# Intan_32.net
KiCad netlist of a schematic drawn in EAGLE
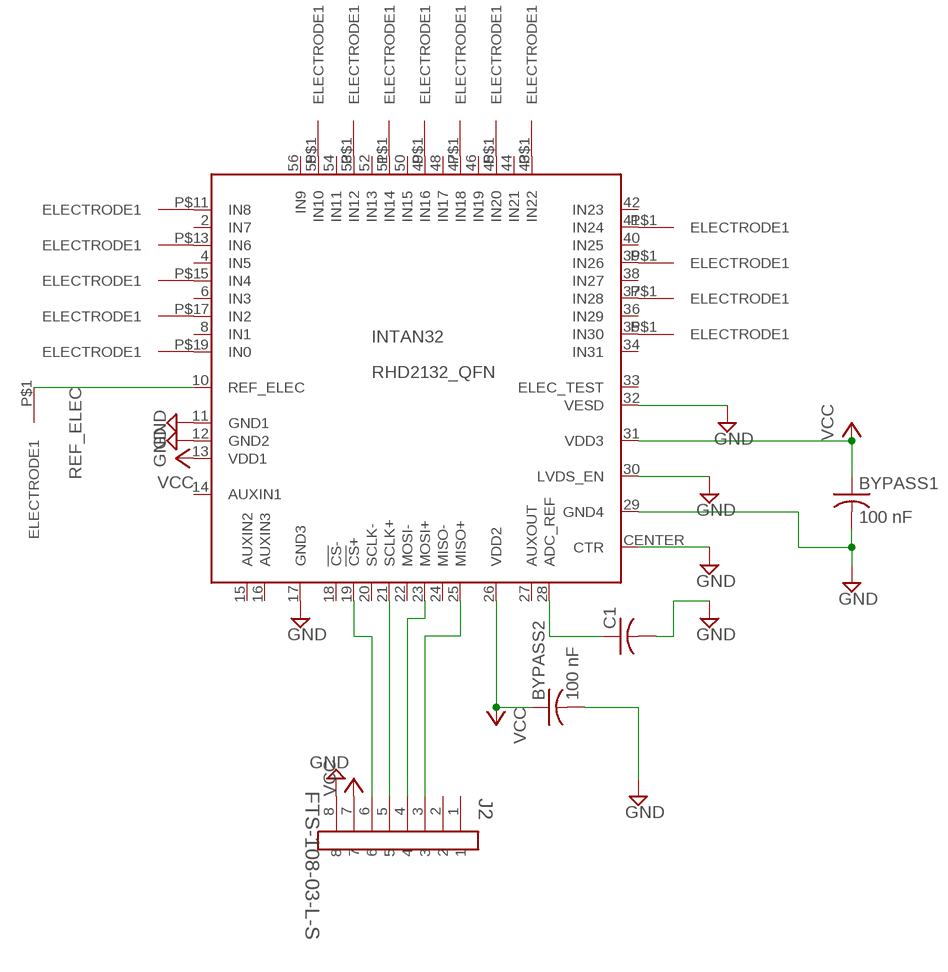
[diagram p0: schematic, sheet 1]

(export (version "E")
  (design (tool "Eeschema 10.0.6"))
  (components
    (comp (ref "BYPASS1")
      (value "100 nF")
      (footprint "eagle-import:C0402")
      (libsource (lib "eagle-import") (part "C-USC0402"))
    )
    (comp (ref "BYPASS2")
      (value "100 nF")
      (footprint "eagle-import:C0402")
      (libsource (lib "eagle-import") (part "C-USC0402"))
    )
    (comp (ref "C1")
      (value "C-USC0402")
      (footprint "eagle-import:C0402")
      (libsource (lib "eagle-import") (part "C-USC0402"))
    )
    (comp (ref "INTAN32")
      (value "RHD2132_QFN")
      (footprint "eagle-import:QFN56_8_X_8_LARGE")
      (libsource (lib "eagle-import") (part "RHD2132_QFN"))
    )
    (comp (ref "J2")
      (value "FTS-108-03-L-S")
      (footprint "eagle-import:SAMTEC_FTS-108-03-S")
      (fields (field (name "MPN") "FTS-108-03-L-D"))
      (libsource (lib "eagle-import") (part "FTS-108-03-L-S"))
    )
    (comp (ref "REF_ELEC")
      (value "INTAN_ELECTRODE_HOLE_2323MIL")
      (footprint "eagle-import:INTAN_ELECTRODE_HOLE_23")
      (libsource (lib "eagle-import") (part "INTAN_ELECTRODE_HOLE_2323MIL"))
    )
    (comp (ref "U$1")
      (value "INTAN_ELECTRODE_HOLE_2323MIL")
      (footprint "eagle-import:INTAN_ELECTRODE_HOLE_23")
      (libsource (lib "eagle-import") (part "INTAN_ELECTRODE_HOLE_2323MIL"))
    )
    (comp (ref "U$2")
      (value "INTAN_ELECTRODE_HOLE_2323MIL")
      (footprint "eagle-import:INTAN_ELECTRODE_HOLE_23")
      (libsource (lib "eagle-import") (part "INTAN_ELECTRODE_HOLE_2323MIL"))
    )
    (comp (ref "U$3")
      (value "INTAN_ELECTRODE_HOLE_2323MIL")
      (footprint "eagle-import:INTAN_ELECTRODE_HOLE_23")
      (libsource (lib "eagle-import") (part "INTAN_ELECTRODE_HOLE_2323MIL"))
    )
    (comp (ref "U$4")
      (value "INTAN_ELECTRODE_HOLE_2323MIL")
      (footprint "eagle-import:INTAN_ELECTRODE_HOLE_23")
      (libsource (lib "eagle-import") (part "INTAN_ELECTRODE_HOLE_2323MIL"))
    )
    (comp (ref "U$5")
      (value "INTAN_ELECTRODE_HOLE_2323MIL")
      (footprint "eagle-import:INTAN_ELECTRODE_HOLE_23")
      (libsource (lib "eagle-import") (part "INTAN_ELECTRODE_HOLE_2323MIL"))
    )
    (comp (ref "U$6")
      (value "INTAN_ELECTRODE_HOLE_2323MIL")
      (footprint "eagle-import:INTAN_ELECTRODE_HOLE_23")
      (libsource (lib "eagle-import") (part "INTAN_ELECTRODE_HOLE_2323MIL"))
    )
    (comp (ref "U$7")
      (value "INTAN_ELECTRODE_HOLE_2323MIL")
      (footprint "eagle-import:INTAN_ELECTRODE_HOLE_23")
      (libsource (lib "eagle-import") (part "INTAN_ELECTRODE_HOLE_2323MIL"))
    )
    (comp (ref "U$8")
      (value "INTAN_ELECTRODE_HOLE_2323MIL")
      (footprint "eagle-import:INTAN_ELECTRODE_HOLE_23")
      (libsource (lib "eagle-import") (part "INTAN_ELECTRODE_HOLE_2323MIL"))
    )
    (comp (ref "U$9")
      (value "INTAN_ELECTRODE_HOLE_2323MIL")
      (footprint "eagle-import:INTAN_ELECTRODE_HOLE_23")
      (libsource (lib "eagle-import") (part "INTAN_ELECTRODE_HOLE_2323MIL"))
    )
    (comp (ref "U$10")
      (value "INTAN_ELECTRODE_HOLE_2323MIL")
      (footprint "eagle-import:INTAN_ELECTRODE_HOLE_23")
      (libsource (lib "eagle-import") (part "INTAN_ELECTRODE_HOLE_2323MIL"))
    )
    (comp (ref "U$11")
      (value "INTAN_ELECTRODE_HOLE_2323MIL")
      (footprint "eagle-import:INTAN_ELECTRODE_HOLE_23")
      (libsource (lib "eagle-import") (part "INTAN_ELECTRODE_HOLE_2323MIL"))
    )
    (comp (ref "U$12")
      (value "INTAN_ELECTRODE_HOLE_2323MIL")
      (footprint "eagle-import:INTAN_ELECTRODE_HOLE_23")
      (libsource (lib "eagle-import") (part "INTAN_ELECTRODE_HOLE_2323MIL"))
    )
    (comp (ref "U$13")
      (value "INTAN_ELECTRODE_HOLE_2323MIL")
      (footprint "eagle-import:INTAN_ELECTRODE_HOLE_23")
      (libsource (lib "eagle-import") (part "INTAN_ELECTRODE_HOLE_2323MIL"))
    )
    (comp (ref "U$14")
      (value "INTAN_ELECTRODE_HOLE_2323MIL")
      (footprint "eagle-import:INTAN_ELECTRODE_HOLE_23")
      (libsource (lib "eagle-import") (part "INTAN_ELECTRODE_HOLE_2323MIL"))
    )
    (comp (ref "U$15")
      (value "INTAN_ELECTRODE_HOLE_2323MIL")
      (footprint "eagle-import:INTAN_ELECTRODE_HOLE_23")
      (libsource (lib "eagle-import") (part "INTAN_ELECTRODE_HOLE_2323MIL"))
    )
    (comp (ref "U$16")
      (value "INTAN_ELECTRODE_HOLE_2323MIL")
      (footprint "eagle-import:INTAN_ELECTRODE_HOLE_23")
      (libsource (lib "eagle-import") (part "INTAN_ELECTRODE_HOLE_2323MIL"))
    )
  )
  (nets
    (net (code "1") (name "/REF_ELEC") (class "Default")
      (node (ref "INTAN32") (pin "10") (pinfunction "REF_ELEC_10") (pintype "input"))
      (node (ref "REF_ELEC") (pin "P$1") (pinfunction "ELECTRODE1_P$1") (pintype "bidirectional"))
    )
    (net (code "2") (name "GND") (class "Default")
      (node (ref "BYPASS1") (pin "2") (pinfunction "2_2") (pintype "passive"))
      (node (ref "BYPASS2") (pin "2") (pinfunction "2_2") (pintype "passive"))
      (node (ref "C1") (pin "2") (pinfunction "2_2") (pintype "passive"))
      (node (ref "INTAN32") (pin "11") (pinfunction "GND1_11") (pintype "power_in"))
      (node (ref "INTAN32") (pin "12") (pinfunction "GND2_12") (pintype "power_in"))
      (node (ref "INTAN32") (pin "17") (pinfunction "GND3_17") (pintype "power_in"))
      (node (ref "INTAN32") (pin "29") (pinfunction "GND4_29") (pintype "power_in"))
      (node (ref "INTAN32") (pin "30") (pinfunction "LVDS_EN_30") (pintype "input"))
      (node (ref "INTAN32") (pin "32") (pinfunction "VESD_32") (pintype "power_in"))
      (node (ref "INTAN32") (pin "CENTER") (pinfunction "CTR_CENTER") (pintype "power_in"))
      (node (ref "J2") (pin "8") (pinfunction "8_8") (pintype "passive"))
    )
    (net (code "3") (name "Net-(INTAN32-ADC_REF)") (class "Default")
      (node (ref "C1") (pin "1") (pinfunction "1_1") (pintype "passive"))
      (node (ref "INTAN32") (pin "28") (pinfunction "ADC_REF_28") (pintype "passive"))
    )
    (net (code "4") (name "Net-(INTAN32-IN0)") (class "Default")
      (node (ref "INTAN32") (pin "9") (pinfunction "IN0_9") (pintype "input"))
      (node (ref "U$1") (pin "P$1") (pinfunction "ELECTRODE1_P$1") (pintype "bidirectional"))
    )
    (net (code "5") (name "Net-(INTAN32-IN2)") (class "Default")
      (node (ref "INTAN32") (pin "7") (pinfunction "IN2_7") (pintype "input"))
      (node (ref "U$2") (pin "P$1") (pinfunction "ELECTRODE1_P$1") (pintype "bidirectional"))
    )
    (net (code "6") (name "Net-(INTAN32-IN4)") (class "Default")
      (node (ref "INTAN32") (pin "5") (pinfunction "IN4_5") (pintype "input"))
      (node (ref "U$3") (pin "P$1") (pinfunction "ELECTRODE1_P$1") (pintype "bidirectional"))
    )
    (net (code "7") (name "Net-(INTAN32-IN6)") (class "Default")
      (node (ref "INTAN32") (pin "3") (pinfunction "IN6_3") (pintype "input"))
      (node (ref "U$4") (pin "P$1") (pinfunction "ELECTRODE1_P$1") (pintype "bidirectional"))
    )
    (net (code "8") (name "Net-(INTAN32-IN8)") (class "Default")
      (node (ref "INTAN32") (pin "1") (pinfunction "IN8_1") (pintype "input"))
      (node (ref "U$5") (pin "P$1") (pinfunction "ELECTRODE1_P$1") (pintype "bidirectional"))
    )
    (net (code "9") (name "Net-(INTAN32-IN10)") (class "Default")
      (node (ref "INTAN32") (pin "55") (pinfunction "IN10_55") (pintype "input"))
      (node (ref "U$6") (pin "P$1") (pinfunction "ELECTRODE1_P$1") (pintype "bidirectional"))
    )
    (net (code "10") (name "Net-(INTAN32-IN12)") (class "Default")
      (node (ref "INTAN32") (pin "53") (pinfunction "IN12_53") (pintype "input"))
      (node (ref "U$7") (pin "P$1") (pinfunction "ELECTRODE1_P$1") (pintype "bidirectional"))
    )
    (net (code "11") (name "Net-(INTAN32-IN14)") (class "Default")
      (node (ref "INTAN32") (pin "51") (pinfunction "IN14_51") (pintype "input"))
      (node (ref "U$8") (pin "P$1") (pinfunction "ELECTRODE1_P$1") (pintype "bidirectional"))
    )
    (net (code "12") (name "Net-(INTAN32-IN16)") (class "Default")
      (node (ref "INTAN32") (pin "49") (pinfunction "IN16_49") (pintype "input"))
      (node (ref "U$9") (pin "P$1") (pinfunction "ELECTRODE1_P$1") (pintype "bidirectional"))
    )
    (net (code "13") (name "Net-(INTAN32-IN18)") (class "Default")
      (node (ref "INTAN32") (pin "47") (pinfunction "IN18_47") (pintype "input"))
      (node (ref "U$10") (pin "P$1") (pinfunction "ELECTRODE1_P$1") (pintype "bidirectional"))
    )
    (net (code "14") (name "Net-(INTAN32-IN20)") (class "Default")
      (node (ref "INTAN32") (pin "45") (pinfunction "IN20_45") (pintype "input"))
      (node (ref "U$11") (pin "P$1") (pinfunction "ELECTRODE1_P$1") (pintype "bidirectional"))
    )
    (net (code "15") (name "Net-(INTAN32-IN22)") (class "Default")
      (node (ref "INTAN32") (pin "43") (pinfunction "IN22_43") (pintype "input"))
      (node (ref "U$12") (pin "P$1") (pinfunction "ELECTRODE1_P$1") (pintype "bidirectional"))
    )
    (net (code "16") (name "Net-(INTAN32-IN24)") (class "Default")
      (node (ref "INTAN32") (pin "41") (pinfunction "IN24_41") (pintype "input"))
      (node (ref "U$13") (pin "P$1") (pinfunction "ELECTRODE1_P$1") (pintype "bidirectional"))
    )
    (net (code "17") (name "Net-(INTAN32-IN26)") (class "Default")
      (node (ref "INTAN32") (pin "39") (pinfunction "IN26_39") (pintype "input"))
      (node (ref "U$14") (pin "P$1") (pinfunction "ELECTRODE1_P$1") (pintype "bidirectional"))
    )
    (net (code "18") (name "Net-(INTAN32-IN28)") (class "Default")
      (node (ref "INTAN32") (pin "37") (pinfunction "IN28_37") (pintype "input"))
      (node (ref "U$15") (pin "P$1") (pinfunction "ELECTRODE1_P$1") (pintype "bidirectional"))
    )
    (net (code "19") (name "Net-(INTAN32-IN30)") (class "Default")
      (node (ref "INTAN32") (pin "35") (pinfunction "IN30_35") (pintype "input"))
      (node (ref "U$16") (pin "P$1") (pinfunction "ELECTRODE1_P$1") (pintype "bidirectional"))
    )
    (net (code "20") (name "Net-(INTAN32-MISO+)") (class "Default")
      (node (ref "INTAN32") (pin "25") (pinfunction "MISO+_25") (pintype "output"))
      (node (ref "J2") (pin "3") (pinfunction "3_3") (pintype "passive"))
    )
    (net (code "21") (name "Net-(INTAN32-MOSI+)") (class "Default")
      (node (ref "INTAN32") (pin "23") (pinfunction "MOSI+_23") (pintype "input"))
      (node (ref "J2") (pin "4") (pinfunction "4_4") (pintype "passive"))
    )
    (net (code "22") (name "Net-(INTAN32-SCLK+)") (class "Default")
      (node (ref "INTAN32") (pin "21") (pinfunction "SCLK+_21") (pintype "input"))
      (node (ref "J2") (pin "5") (pinfunction "5_5") (pintype "passive"))
    )
    (net (code "23") (name "Net-(INTAN32-~{CS}+)") (class "Default")
      (node (ref "INTAN32") (pin "19") (pinfunction "~{CS}+_19") (pintype "input"))
      (node (ref "J2") (pin "6") (pinfunction "6_6") (pintype "passive"))
    )
    (net (code "24") (name "VCC") (class "Default")
      (node (ref "BYPASS1") (pin "1") (pinfunction "1_1") (pintype "passive"))
      (node (ref "BYPASS2") (pin "1") (pinfunction "1_1") (pintype "passive"))
      (node (ref "INTAN32") (pin "13") (pinfunction "VDD1_13") (pintype "power_in"))
      (node (ref "INTAN32") (pin "26") (pinfunction "VDD2_26") (pintype "power_in"))
      (node (ref "INTAN32") (pin "31") (pinfunction "VDD3_31") (pintype "power_in"))
      (node (ref "J2") (pin "7") (pinfunction "7_7") (pintype "passive"))
    )
    (net (code "25") (name "unconnected-(INTAN32-AUXIN1-Pad14)") (class "Default")
      (node (ref "INTAN32") (pin "14") (pinfunction "AUXIN1_14") (pintype "input"))
    )
    (net (code "26") (name "unconnected-(INTAN32-AUXIN2-Pad15)") (class "Default")
      (node (ref "INTAN32") (pin "15") (pinfunction "AUXIN2_15") (pintype "input"))
    )
    (net (code "27") (name "unconnected-(INTAN32-AUXIN3-Pad16)") (class "Default")
      (node (ref "INTAN32") (pin "16") (pinfunction "AUXIN3_16") (pintype "input"))
    )
    (net (code "28") (name "unconnected-(INTAN32-AUXOUT-Pad27)") (class "Default")
      (node (ref "INTAN32") (pin "27") (pinfunction "AUXOUT_27") (pintype "tri_state"))
    )
    (net (code "29") (name "unconnected-(INTAN32-ELEC_TEST-Pad33)") (class "Default")
      (node (ref "INTAN32") (pin "33") (pinfunction "ELEC_TEST_33") (pintype "input"))
    )
    (net (code "30") (name "unconnected-(INTAN32-IN1-Pad8)") (class "Default")
      (node (ref "INTAN32") (pin "8") (pinfunction "IN1_8") (pintype "input"))
    )
    (net (code "31") (name "unconnected-(INTAN32-IN3-Pad6)") (class "Default")
      (node (ref "INTAN32") (pin "6") (pinfunction "IN3_6") (pintype "input"))
    )
    (net (code "32") (name "unconnected-(INTAN32-IN5-Pad4)") (class "Default")
      (node (ref "INTAN32") (pin "4") (pinfunction "IN5_4") (pintype "input"))
    )
    (net (code "33") (name "unconnected-(INTAN32-IN7-Pad2)") (class "Default")
      (node (ref "INTAN32") (pin "2") (pinfunction "IN7_2") (pintype "input"))
    )
    (net (code "34") (name "unconnected-(INTAN32-IN9-Pad56)") (class "Default")
      (node (ref "INTAN32") (pin "56") (pinfunction "IN9_56") (pintype "input"))
    )
    (net (code "35") (name "unconnected-(INTAN32-IN11-Pad54)") (class "Default")
      (node (ref "INTAN32") (pin "54") (pinfunction "IN11_54") (pintype "input"))
    )
    (net (code "36") (name "unconnected-(INTAN32-IN13-Pad52)") (class "Default")
      (node (ref "INTAN32") (pin "52") (pinfunction "IN13_52") (pintype "input"))
    )
    (net (code "37") (name "unconnected-(INTAN32-IN15-Pad50)") (class "Default")
      (node (ref "INTAN32") (pin "50") (pinfunction "IN15_50") (pintype "input"))
    )
    (net (code "38") (name "unconnected-(INTAN32-IN17-Pad48)") (class "Default")
      (node (ref "INTAN32") (pin "48") (pinfunction "IN17_48") (pintype "input"))
    )
    (net (code "39") (name "unconnected-(INTAN32-IN19-Pad46)") (class "Default")
      (node (ref "INTAN32") (pin "46") (pinfunction "IN19_46") (pintype "input"))
    )
    (net (code "40") (name "unconnected-(INTAN32-IN21-Pad44)") (class "Default")
      (node (ref "INTAN32") (pin "44") (pinfunction "IN21_44") (pintype "input"))
    )
    (net (code "41") (name "unconnected-(INTAN32-IN23-Pad42)") (class "Default")
      (node (ref "INTAN32") (pin "42") (pinfunction "IN23_42") (pintype "input"))
    )
    (net (code "42") (name "unconnected-(INTAN32-IN25-Pad40)") (class "Default")
      (node (ref "INTAN32") (pin "40") (pinfunction "IN25_40") (pintype "input"))
    )
    (net (code "43") (name "unconnected-(INTAN32-IN27-Pad38)") (class "Default")
      (node (ref "INTAN32") (pin "38") (pinfunction "IN27_38") (pintype "input"))
    )
    (net (code "44") (name "unconnected-(INTAN32-IN29-Pad36)") (class "Default")
      (node (ref "INTAN32") (pin "36") (pinfunction "IN29_36") (pintype "input"))
    )
    (net (code "45") (name "unconnected-(INTAN32-IN31-Pad34)") (class "Default")
      (node (ref "INTAN32") (pin "34") (pinfunction "IN31_34") (pintype "input"))
    )
    (net (code "46") (name "unconnected-(INTAN32-MISO--Pad24)") (class "Default")
      (node (ref "INTAN32") (pin "24") (pinfunction "MISO-_24") (pintype "output"))
    )
    (net (code "47") (name "unconnected-(INTAN32-MOSI--Pad22)") (class "Default")
      (node (ref "INTAN32") (pin "22") (pinfunction "MOSI-_22") (pintype "input"))
    )
    (net (code "48") (name "unconnected-(INTAN32-SCLK--Pad20)") (class "Default")
      (node (ref "INTAN32") (pin "20") (pinfunction "SCLK-_20") (pintype "input"))
    )
    (net (code "49") (name "unconnected-(INTAN32-~{CS}--Pad18)") (class "Default")
      (node (ref "INTAN32") (pin "18") (pinfunction "~{CS}-_18") (pintype "input"))
    )
    (net (code "50") (name "unconnected-(J2-Pad1)") (class "Default")
      (node (ref "J2") (pin "1") (pinfunction "1_1") (pintype "passive"))
    )
    (net (code "51") (name "unconnected-(J2-Pad2)") (class "Default")
      (node (ref "J2") (pin "2") (pinfunction "2_2") (pintype "passive"))
    )
  )
)
